# UPF_BTB_TESTBOARD.net
KiCad netlist of a schematic drawn in Altium Designer
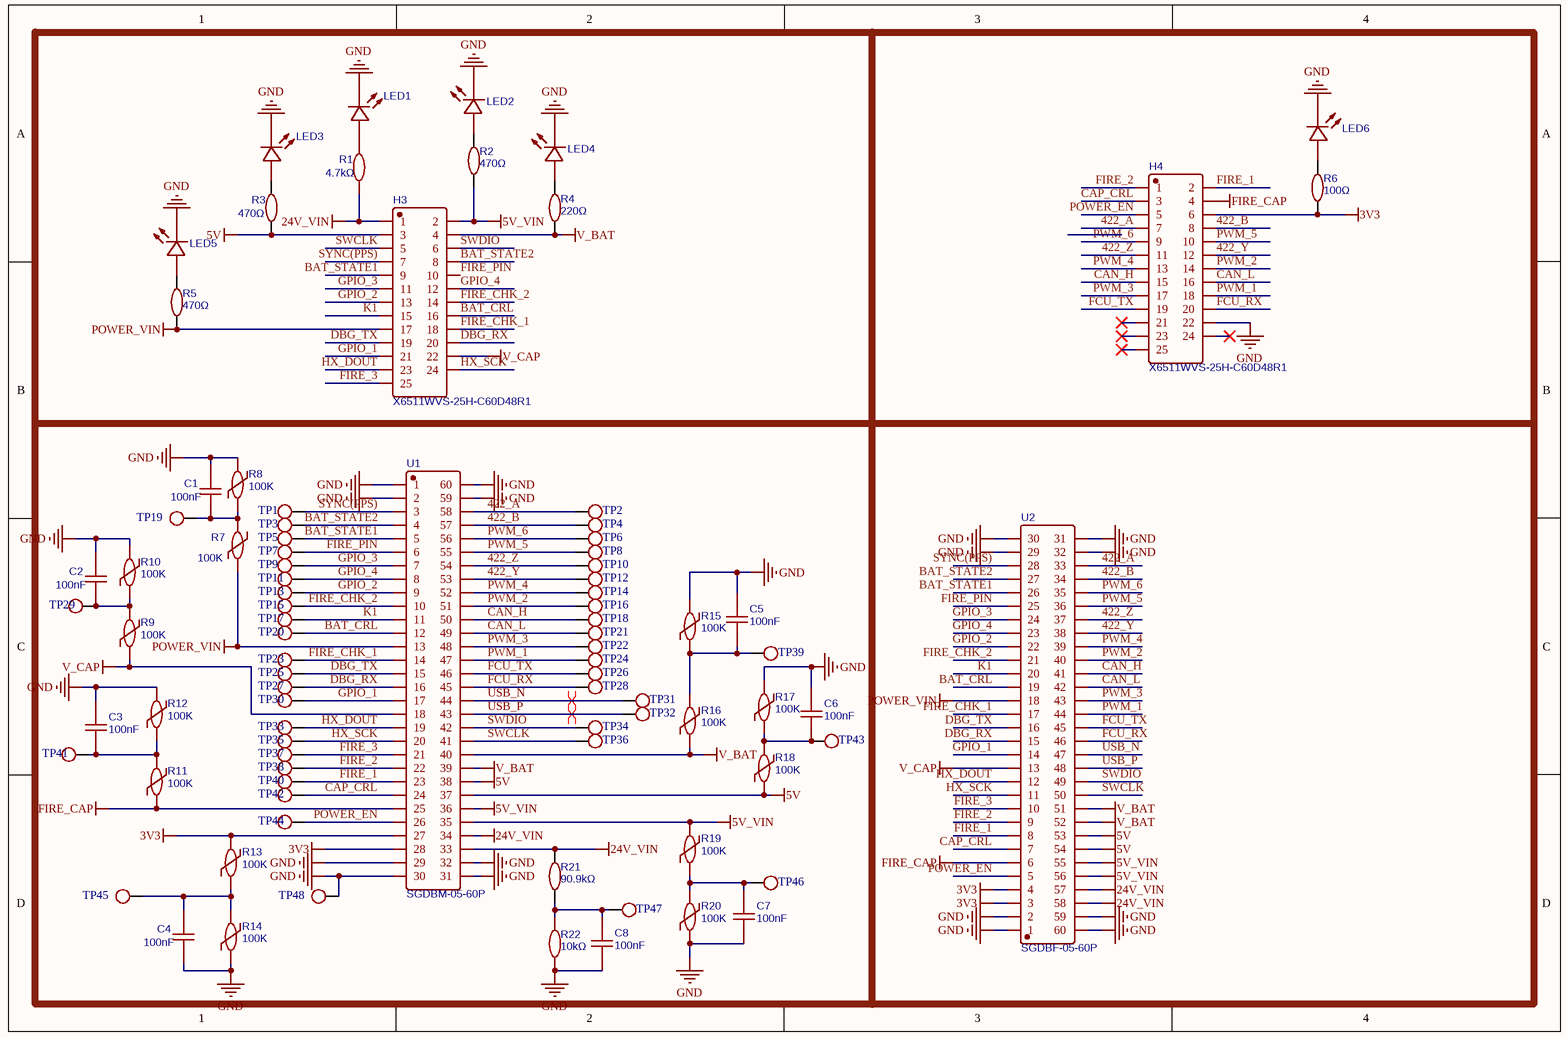
[diagram p0: UPF_BTB_TESTBOARD.SchDoc]

(export (version "E")
  (design (tool "Eeschema 10.0.6"))
  (components
    (comp (ref "C1")
      (value "100nF")
      (footprint "C0603")
      (fields
        (field (name "BOM_SUPPLIER PART") "C327087")
        (field (name "BOM_MANUFACTURER PART") "CC0603JRX7R8BB104")
        (field (name "CONTRIBUTOR") "LCSC")
      )
      (libsource (lib "C0603_100nF") (part "100nF"))
    )
    (comp (ref "C2")
      (value "100nF")
      (footprint "C0603")
      (fields
        (field (name "BOM_SUPPLIER PART") "C327087")
        (field (name "BOM_MANUFACTURER PART") "CC0603JRX7R8BB104")
        (field (name "CONTRIBUTOR") "LCSC")
      )
      (libsource (lib "C0603_100nF") (part "100nF"))
    )
    (comp (ref "C3")
      (value "100nF")
      (footprint "C0603")
      (fields
        (field (name "BOM_SUPPLIER PART") "C327087")
        (field (name "BOM_MANUFACTURER PART") "CC0603JRX7R8BB104")
        (field (name "CONTRIBUTOR") "LCSC")
      )
      (libsource (lib "C0603_100nF") (part "100nF"))
    )
    (comp (ref "C4")
      (value "100nF")
      (footprint "C0603")
      (fields
        (field (name "BOM_SUPPLIER PART") "C327087")
        (field (name "BOM_MANUFACTURER PART") "CC0603JRX7R8BB104")
        (field (name "CONTRIBUTOR") "LCSC")
      )
      (libsource (lib "C0603_100nF") (part "100nF"))
    )
    (comp (ref "C5")
      (value "100nF")
      (footprint "C0603")
      (fields
        (field (name "BOM_SUPPLIER PART") "C327087")
        (field (name "BOM_MANUFACTURER PART") "CC0603JRX7R8BB104")
        (field (name "CONTRIBUTOR") "LCSC")
      )
      (libsource (lib "C0603_100nF") (part "100nF"))
    )
    (comp (ref "C6")
      (value "100nF")
      (footprint "C0603")
      (fields
        (field (name "BOM_SUPPLIER PART") "C327087")
        (field (name "BOM_MANUFACTURER PART") "CC0603JRX7R8BB104")
        (field (name "CONTRIBUTOR") "LCSC")
      )
      (libsource (lib "C0603_100nF") (part "100nF"))
    )
    (comp (ref "C7")
      (value "100nF")
      (footprint "C0603")
      (fields
        (field (name "BOM_SUPPLIER PART") "C327087")
        (field (name "BOM_MANUFACTURER PART") "CC0603JRX7R8BB104")
        (field (name "CONTRIBUTOR") "LCSC")
      )
      (libsource (lib "C0603_100nF") (part "100nF"))
    )
    (comp (ref "C8")
      (value "100nF")
      (footprint "C0603")
      (fields
        (field (name "BOM_SUPPLIER PART") "C327087")
        (field (name "BOM_MANUFACTURER PART") "CC0603JRX7R8BB104")
        (field (name "CONTRIBUTOR") "LCSC")
      )
      (libsource (lib "C0603_100nF") (part "100nF"))
    )
    (comp (ref "H3")
      (value "X6511WVS-25H-C60D48R1")
      (footprint "HDR-SMD_25P-P2.54_XKB_X6511WVS-25H-C60D48R1")
      (fields (field (name "BOM_SUPPLIER PART") "C2883821") (field (name "CONTRIBUTOR") "LCSC"))
      (libsource (lib "X6511WVS-25H-C60D48R1") (part "X6511WVS-25H-C60D48R1"))
    )
    (comp (ref "H4")
      (value "X6511WVS-25H-C60D48R1")
      (footprint "HDR-SMD_25P-P2.54_XKB_X6511WVS-25H-C60D48R1")
      (fields (field (name "BOM_SUPPLIER PART") "C2883821") (field (name "CONTRIBUTOR") "LCSC"))
      (libsource (lib "X6511WVS-25H-C60D48R1") (part "X6511WVS-25H-C60D48R1"))
    )
    (comp (ref "LED1")
      (value "FC-F1005YGK-572J5")
      (footprint "LED0402-RD")
      (fields (field (name "BOM_SUPPLIER PART") "C130722") (field (name "CONTRIBUTOR") "LCSC"))
      (libsource (lib "LED_GREEN") (part "FC-F1005YGK-572J5"))
    )
    (comp (ref "LED2")
      (value "FC-F1005YGK-572J5")
      (footprint "LED0402-RD")
      (fields (field (name "BOM_SUPPLIER PART") "C130722") (field (name "CONTRIBUTOR") "LCSC"))
      (libsource (lib "LED_GREEN") (part "FC-F1005YGK-572J5"))
    )
    (comp (ref "LED3")
      (value "FC-F1005YGK-572J5")
      (footprint "LED0402-RD")
      (fields (field (name "BOM_SUPPLIER PART") "C130722") (field (name "CONTRIBUTOR") "LCSC"))
      (libsource (lib "LED_GREEN") (part "FC-F1005YGK-572J5"))
    )
    (comp (ref "LED4")
      (value "FC-F1005YGK-572J5")
      (footprint "LED0402-RD")
      (fields (field (name "BOM_SUPPLIER PART") "C130722") (field (name "CONTRIBUTOR") "LCSC"))
      (libsource (lib "LED_GREEN") (part "FC-F1005YGK-572J5"))
    )
    (comp (ref "LED5")
      (value "FC-F1005YGK-572J5")
      (footprint "LED0402-RD")
      (fields (field (name "BOM_SUPPLIER PART") "C130722") (field (name "CONTRIBUTOR") "LCSC"))
      (libsource (lib "LED_GREEN") (part "FC-F1005YGK-572J5"))
    )
    (comp (ref "LED6")
      (value "FC-F1005YGK-572J5")
      (footprint "LED0402-RD")
      (fields (field (name "BOM_SUPPLIER PART") "C130722") (field (name "CONTRIBUTOR") "LCSC"))
      (libsource (lib "LED_GREEN") (part "FC-F1005YGK-572J5"))
    )
    (comp (ref "R1")
      (value "4.7kΩ")
      (footprint "R0402")
      (fields
        (field (name "BOM_SUPPLIER PART") "C270129")
        (field (name "BOM_MANUFACTURER PART") "RMC04024.7K1%N")
        (field (name "CONTRIBUTOR") "LCSC")
      )
      (libsource (lib "R0402_4k7") (part "4.7kΩ"))
    )
    (comp (ref "R2")
      (value "470Ω")
      (footprint "R0402")
      (fields
        (field (name "BOM_MANUFACTURER PART") "CR0402FF4700G")
        (field (name "BOM_SUPPLIER PART") "C100443")
      )
      (libsource (lib "R0402_470") (part "470Ω"))
    )
    (comp (ref "R3")
      (value "470Ω")
      (footprint "R0402")
      (fields
        (field (name "BOM_MANUFACTURER PART") "CR0402FF4700G")
        (field (name "BOM_SUPPLIER PART") "C100443")
      )
      (libsource (lib "R0402_470") (part "470Ω"))
    )
    (comp (ref "R4")
      (value "220Ω")
      (footprint "R0402")
      (fields
        (field (name "BOM_MANUFACTURER PART") "CR0402FF2200G")
        (field (name "BOM_SUPPLIER PART") "C100308")
        (field (name "CONTRIBUTOR") "LCSC")
      )
      (libsource (lib "R0402_220") (part "220Ω"))
    )
    (comp (ref "R5")
      (value "470Ω")
      (footprint "R0402")
      (fields
        (field (name "BOM_MANUFACTURER PART") "CR0402FF4700G")
        (field (name "BOM_SUPPLIER PART") "C100443")
      )
      (libsource (lib "R0402_470") (part "470Ω"))
    )
    (comp (ref "R6")
      (value "100Ω")
      (footprint "R0402")
      (fields
        (field (name "BOM_MANUFACTURER PART") "CR0402FF1000G")
        (field (name "BOM_SUPPLIER PART") "C100194")
      )
      (libsource (lib "R0402_100") (part "100Ω"))
    )
    (comp (ref "R7")
      (value "100K")
      (footprint "R0603")
      (fields
        (field (name "BOM_SUPPLIER PART") "C388278")
        (field (name "BOM_MANUFACTURER PART") "TCTR0603F100KF4260T")
        (field (name "CONTRIBUTOR") "LCSC")
      )
      (libsource (lib "R0603_100K") (part "100K"))
    )
    (comp (ref "R8")
      (value "100K")
      (footprint "R0603")
      (fields
        (field (name "BOM_SUPPLIER PART") "C388278")
        (field (name "BOM_MANUFACTURER PART") "TCTR0603F100KF4260T")
        (field (name "CONTRIBUTOR") "LCSC")
      )
      (libsource (lib "R0603_100K") (part "100K"))
    )
    (comp (ref "R9")
      (value "100K")
      (footprint "R0603")
      (fields
        (field (name "BOM_SUPPLIER PART") "C388278")
        (field (name "BOM_MANUFACTURER PART") "TCTR0603F100KF4260T")
        (field (name "CONTRIBUTOR") "LCSC")
      )
      (libsource (lib "R0603_100K") (part "100K"))
    )
    (comp (ref "R10")
      (value "100K")
      (footprint "R0603")
      (fields
        (field (name "BOM_SUPPLIER PART") "C388278")
        (field (name "BOM_MANUFACTURER PART") "TCTR0603F100KF4260T")
        (field (name "CONTRIBUTOR") "LCSC")
      )
      (libsource (lib "R0603_100K") (part "100K"))
    )
    (comp (ref "R11")
      (value "100K")
      (footprint "R0603")
      (fields
        (field (name "BOM_SUPPLIER PART") "C388278")
        (field (name "BOM_MANUFACTURER PART") "TCTR0603F100KF4260T")
        (field (name "CONTRIBUTOR") "LCSC")
      )
      (libsource (lib "R0603_100K") (part "100K"))
    )
    (comp (ref "R12")
      (value "100K")
      (footprint "R0603")
      (fields
        (field (name "BOM_SUPPLIER PART") "C388278")
        (field (name "BOM_MANUFACTURER PART") "TCTR0603F100KF4260T")
        (field (name "CONTRIBUTOR") "LCSC")
      )
      (libsource (lib "R0603_100K") (part "100K"))
    )
    (comp (ref "R13")
      (value "100K")
      (footprint "R0603")
      (fields
        (field (name "BOM_SUPPLIER PART") "C388278")
        (field (name "BOM_MANUFACTURER PART") "TCTR0603F100KF4260T")
        (field (name "CONTRIBUTOR") "LCSC")
      )
      (libsource (lib "R0603_100K") (part "100K"))
    )
    (comp (ref "R14")
      (value "100K")
      (footprint "R0603")
      (fields
        (field (name "BOM_SUPPLIER PART") "C388278")
        (field (name "BOM_MANUFACTURER PART") "TCTR0603F100KF4260T")
        (field (name "CONTRIBUTOR") "LCSC")
      )
      (libsource (lib "R0603_100K") (part "100K"))
    )
    (comp (ref "R15")
      (value "100K")
      (footprint "R0603")
      (fields
        (field (name "BOM_SUPPLIER PART") "C388278")
        (field (name "BOM_MANUFACTURER PART") "TCTR0603F100KF4260T")
        (field (name "CONTRIBUTOR") "LCSC")
      )
      (libsource (lib "R0603_100K") (part "100K"))
    )
    (comp (ref "R16")
      (value "100K")
      (footprint "R0603")
      (fields
        (field (name "BOM_SUPPLIER PART") "C388278")
        (field (name "BOM_MANUFACTURER PART") "TCTR0603F100KF4260T")
        (field (name "CONTRIBUTOR") "LCSC")
      )
      (libsource (lib "R0603_100K") (part "100K"))
    )
    (comp (ref "R17")
      (value "100K")
      (footprint "R0603")
      (fields
        (field (name "BOM_SUPPLIER PART") "C388278")
        (field (name "BOM_MANUFACTURER PART") "TCTR0603F100KF4260T")
        (field (name "CONTRIBUTOR") "LCSC")
      )
      (libsource (lib "R0603_100K") (part "100K"))
    )
    (comp (ref "R18")
      (value "100K")
      (footprint "R0603")
      (fields
        (field (name "BOM_SUPPLIER PART") "C388278")
        (field (name "BOM_MANUFACTURER PART") "TCTR0603F100KF4260T")
        (field (name "CONTRIBUTOR") "LCSC")
      )
      (libsource (lib "R0603_100K") (part "100K"))
    )
    (comp (ref "R19")
      (value "100K")
      (footprint "R0603")
      (fields
        (field (name "BOM_SUPPLIER PART") "C388278")
        (field (name "BOM_MANUFACTURER PART") "TCTR0603F100KF4260T")
        (field (name "CONTRIBUTOR") "LCSC")
      )
      (libsource (lib "R0603_100K") (part "100K"))
    )
    (comp (ref "R20")
      (value "100K")
      (footprint "R0603")
      (fields
        (field (name "BOM_SUPPLIER PART") "C388278")
        (field (name "BOM_MANUFACTURER PART") "TCTR0603F100KF4260T")
        (field (name "CONTRIBUTOR") "LCSC")
      )
      (libsource (lib "R0603_100K") (part "100K"))
    )
    (comp (ref "R21")
      (value "90.9kΩ")
      (footprint "R0603")
      (fields
        (field (name "BOM_MANUFACTURER PART") "RS-03K9092FT")
        (field (name "BOM_SUPPLIER PART") "C140067")
      )
      (libsource (lib "R0603_90.9K") (part "90.9kΩ"))
    )
    (comp (ref "R22")
      (value "10kΩ")
      (footprint "R0603")
      (fields
        (field (name "BOM_SUPPLIER PART") "C188363")
        (field (name "BOM_MANUFACTURER PART") "TR0603B10KP05250.1W")
        (field (name "CONTRIBUTOR") "LCSC")
      )
      (libsource (lib "R0603_10K") (part "10kΩ"))
    )
    (comp (ref "TP1")
      (value "TP5")
      (footprint "TP2")
      (description "测试点/单焊盘")
      (libsource (lib "五金器件") (part "TP5"))
    )
    (comp (ref "TP2")
      (value "TP5")
      (footprint "TP2")
      (description "测试点/单焊盘")
      (libsource (lib "五金器件") (part "TP5"))
    )
    (comp (ref "TP3")
      (value "TP5")
      (footprint "TP2")
      (description "测试点/单焊盘")
      (libsource (lib "五金器件") (part "TP5"))
    )
    (comp (ref "TP4")
      (value "TP5")
      (footprint "TP2")
      (description "测试点/单焊盘")
      (libsource (lib "五金器件") (part "TP5"))
    )
    (comp (ref "TP5")
      (value "TP5")
      (footprint "TP2")
      (description "测试点/单焊盘")
      (libsource (lib "五金器件") (part "TP5"))
    )
    (comp (ref "TP6")
      (value "TP5")
      (footprint "TP2")
      (description "测试点/单焊盘")
      (libsource (lib "五金器件") (part "TP5"))
    )
    (comp (ref "TP7")
      (value "TP5")
      (footprint "TP2")
      (description "测试点/单焊盘")
      (libsource (lib "五金器件") (part "TP5"))
    )
    (comp (ref "TP8")
      (value "TP5")
      (footprint "TP2")
      (description "测试点/单焊盘")
      (libsource (lib "五金器件") (part "TP5"))
    )
    (comp (ref "TP9")
      (value "TP5")
      (footprint "TP2")
      (description "测试点/单焊盘")
      (libsource (lib "五金器件") (part "TP5"))
    )
    (comp (ref "TP10")
      (value "TP5")
      (footprint "TP2")
      (description "测试点/单焊盘")
      (libsource (lib "五金器件") (part "TP5"))
    )
    (comp (ref "TP11")
      (value "TP5")
      (footprint "TP2")
      (description "测试点/单焊盘")
      (libsource (lib "五金器件") (part "TP5"))
    )
    (comp (ref "TP12")
      (value "TP5")
      (footprint "TP2")
      (description "测试点/单焊盘")
      (libsource (lib "五金器件") (part "TP5"))
    )
    (comp (ref "TP13")
      (value "TP5")
      (footprint "TP2")
      (description "测试点/单焊盘")
      (libsource (lib "五金器件") (part "TP5"))
    )
    (comp (ref "TP14")
      (value "TP5")
      (footprint "TP2")
      (description "测试点/单焊盘")
      (libsource (lib "五金器件") (part "TP5"))
    )
    (comp (ref "TP15")
      (value "TP5")
      (footprint "TP2")
      (description "测试点/单焊盘")
      (libsource (lib "五金器件") (part "TP5"))
    )
    (comp (ref "TP16")
      (value "TP5")
      (footprint "TP2")
      (description "测试点/单焊盘")
      (libsource (lib "五金器件") (part "TP5"))
    )
    (comp (ref "TP17")
      (value "TP5")
      (footprint "TP2")
      (description "测试点/单焊盘")
      (libsource (lib "五金器件") (part "TP5"))
    )
    (comp (ref "TP18")
      (value "TP5")
      (footprint "TP2")
      (description "测试点/单焊盘")
      (libsource (lib "五金器件") (part "TP5"))
    )
    (comp (ref "TP19")
      (value "TP5")
      (footprint "TP2")
      (description "测试点/单焊盘")
      (libsource (lib "五金器件") (part "TP5"))
    )
    (comp (ref "TP20")
      (value "TP5")
      (footprint "TP2")
      (description "测试点/单焊盘")
      (libsource (lib "五金器件") (part "TP5"))
    )
    (comp (ref "TP21")
      (value "TP5")
      (footprint "TP2")
      (description "测试点/单焊盘")
      (libsource (lib "五金器件") (part "TP5"))
    )
    (comp (ref "TP22")
      (value "TP5")
      (footprint "TP2")
      (description "测试点/单焊盘")
      (libsource (lib "五金器件") (part "TP5"))
    )
    (comp (ref "TP23")
      (value "TP5")
      (footprint "TP2")
      (description "测试点/单焊盘")
      (libsource (lib "五金器件") (part "TP5"))
    )
    (comp (ref "TP24")
      (value "TP5")
      (footprint "TP2")
      (description "测试点/单焊盘")
      (libsource (lib "五金器件") (part "TP5"))
    )
    (comp (ref "TP25")
      (value "TP5")
      (footprint "TP2")
      (description "测试点/单焊盘")
      (libsource (lib "五金器件") (part "TP5"))
    )
    (comp (ref "TP26")
      (value "TP5")
      (footprint "TP2")
      (description "测试点/单焊盘")
      (libsource (lib "五金器件") (part "TP5"))
    )
    (comp (ref "TP27")
      (value "TP5")
      (footprint "TP2")
      (description "测试点/单焊盘")
      (libsource (lib "五金器件") (part "TP5"))
    )
    (comp (ref "TP28")
      (value "TP5")
      (footprint "TP2")
      (description "测试点/单焊盘")
      (libsource (lib "五金器件") (part "TP5"))
    )
    (comp (ref "TP29")
      (value "TP5")
      (footprint "TP2")
      (description "测试点/单焊盘")
      (libsource (lib "五金器件") (part "TP5"))
    )
    (comp (ref "TP30")
      (value "TP5")
      (footprint "TP2")
      (description "测试点/单焊盘")
      (libsource (lib "五金器件") (part "TP5"))
    )
    (comp (ref "TP31")
      (value "TP5")
      (footprint "TP2")
      (description "测试点/单焊盘")
      (libsource (lib "五金器件") (part "TP5"))
    )
    (comp (ref "TP32")
      (value "TP5")
      (footprint "TP2")
      (description "测试点/单焊盘")
      (libsource (lib "五金器件") (part "TP5"))
    )
    (comp (ref "TP33")
      (value "TP5")
      (footprint "TP2")
      (description "测试点/单焊盘")
      (libsource (lib "五金器件") (part "TP5"))
    )
    (comp (ref "TP34")
      (value "TP5")
      (footprint "TP2")
      (description "测试点/单焊盘")
      (libsource (lib "五金器件") (part "TP5"))
    )
    (comp (ref "TP35")
      (value "TP5")
      (footprint "TP2")
      (description "测试点/单焊盘")
      (libsource (lib "五金器件") (part "TP5"))
    )
    (comp (ref "TP36")
      (value "TP5")
      (footprint "TP2")
      (description "测试点/单焊盘")
      (libsource (lib "五金器件") (part "TP5"))
    )
    (comp (ref "TP37")
      (value "TP5")
      (footprint "TP2")
      (description "测试点/单焊盘")
      (libsource (lib "五金器件") (part "TP5"))
    )
    (comp (ref "TP38")
      (value "TP5")
      (footprint "TP2")
      (description "测试点/单焊盘")
      (libsource (lib "五金器件") (part "TP5"))
    )
    (comp (ref "TP39")
      (value "TP5")
      (footprint "TP2")
      (description "测试点/单焊盘")
      (libsource (lib "五金器件") (part "TP5"))
    )
    (comp (ref "TP40")
      (value "TP5")
      (footprint "TP2")
      (description "测试点/单焊盘")
      (libsource (lib "五金器件") (part "TP5"))
    )
    (comp (ref "TP41")
      (value "TP5")
      (footprint "TP2")
      (description "测试点/单焊盘")
      (libsource (lib "五金器件") (part "TP5"))
    )
    (comp (ref "TP42")
      (value "TP5")
      (footprint "TP2")
      (description "测试点/单焊盘")
      (libsource (lib "五金器件") (part "TP5"))
    )
    (comp (ref "TP43")
      (value "TP5")
      (footprint "TP2")
      (description "测试点/单焊盘")
      (libsource (lib "五金器件") (part "TP5"))
    )
    (comp (ref "TP44")
      (value "TP5")
      (footprint "TP2")
      (description "测试点/单焊盘")
      (libsource (lib "五金器件") (part "TP5"))
    )
    (comp (ref "TP45")
      (value "TP5")
      (footprint "TP2")
      (description "测试点/单焊盘")
      (libsource (lib "五金器件") (part "TP5"))
    )
    (comp (ref "TP46")
      (value "TP5")
      (footprint "TP2")
      (description "测试点/单焊盘")
      (libsource (lib "五金器件") (part "TP5"))
    )
    (comp (ref "TP47")
      (value "TP5")
      (footprint "TP2")
      (description "测试点/单焊盘")
      (libsource (lib "五金器件") (part "TP5"))
    )
    (comp (ref "TP48")
      (value "TP5")
      (footprint "TP2")
      (description "测试点/单焊盘")
      (libsource (lib "五金器件") (part "TP5"))
    )
    (comp (ref "U1")
      (value "SGDBM-05-60P")
      (footprint "HG-SGDBM-0.5_60P")
      (fields (field (name "BOM_SUPPLIER PART") "C9900010919") (field (name "CONTRIBUTOR") "LCSC"))
      (libsource (lib "SGDBM-05-60P") (part "SGDBM-05-60P"))
    )
    (comp (ref "U2")
      (value "SGDBF-05-60P")
      (footprint "HG-SGDBF-0.5_60P")
      (fields
        (field (name "BOM_SUPPLIER PART") "C9900010919")
        (field (name "BOM_MANUFACTURER PART") "SGDBM-05-60P")
        (field (name "CONTRIBUTOR") "LCSC")
      )
      (libsource (lib "SGDBM-05-60P") (part "SGDBM-05-60P"))
    )
  )
  (nets
    (net (code "1") (name "/422_A") (class "Default")
      (node (ref "H4") (pin "7") (pinfunction "7_7") (pintype "passive"))
      (node (ref "TP2") (pin "1") (pintype "passive"))
      (node (ref "U1") (pin "58") (pinfunction "58_58") (pintype "passive"))
      (node (ref "U2") (pin "33") (pinfunction "33_33") (pintype "passive"))
    )
    (net (code "2") (name "/422_B") (class "Default")
      (node (ref "H4") (pin "8") (pinfunction "8_8") (pintype "passive"))
      (node (ref "TP4") (pin "1") (pintype "passive"))
      (node (ref "U1") (pin "57") (pinfunction "57_57") (pintype "passive"))
      (node (ref "U2") (pin "34") (pinfunction "34_34") (pintype "passive"))
    )
    (net (code "3") (name "/422_Y") (class "Default")
      (node (ref "H4") (pin "12") (pinfunction "12_12") (pintype "passive"))
      (node (ref "TP12") (pin "1") (pintype "passive"))
      (node (ref "U1") (pin "53") (pinfunction "53_53") (pintype "passive"))
      (node (ref "U2") (pin "38") (pinfunction "38_38") (pintype "passive"))
    )
    (net (code "4") (name "/422_Z") (class "Default")
      (node (ref "H4") (pin "11") (pinfunction "11_11") (pintype "passive"))
      (node (ref "TP10") (pin "1") (pintype "passive"))
      (node (ref "U1") (pin "54") (pinfunction "54_54") (pintype "passive"))
      (node (ref "U2") (pin "37") (pinfunction "37_37") (pintype "passive"))
    )
    (net (code "5") (name "/BAT_CRL") (class "Default")
      (node (ref "H3") (pin "16") (pinfunction "16_16") (pintype "passive"))
      (node (ref "TP20") (pin "1") (pintype "passive"))
      (node (ref "U1") (pin "12") (pinfunction "12_12") (pintype "passive"))
      (node (ref "U2") (pin "19") (pinfunction "19_19") (pintype "passive"))
    )
    (net (code "6") (name "/BAT_STATE1") (class "Default")
      (node (ref "H3") (pin "9") (pinfunction "9_9") (pintype "passive"))
      (node (ref "TP5") (pin "1") (pintype "passive"))
      (node (ref "U1") (pin "5") (pinfunction "5_5") (pintype "passive"))
      (node (ref "U2") (pin "26") (pinfunction "26_26") (pintype "passive"))
    )
    (net (code "7") (name "/BAT_STATE2") (class "Default")
      (node (ref "H3") (pin "8") (pinfunction "8_8") (pintype "passive"))
      (node (ref "TP3") (pin "1") (pintype "passive"))
      (node (ref "U1") (pin "4") (pinfunction "4_4") (pintype "passive"))
      (node (ref "U2") (pin "27") (pinfunction "27_27") (pintype "passive"))
    )
    (net (code "8") (name "/CAN_H") (class "Default")
      (node (ref "H4") (pin "15") (pinfunction "15_15") (pintype "passive"))
      (node (ref "TP18") (pin "1") (pintype "passive"))
      (node (ref "U1") (pin "50") (pinfunction "50_50") (pintype "passive"))
      (node (ref "U2") (pin "41") (pinfunction "41_41") (pintype "passive"))
    )
    (net (code "9") (name "/CAN_L") (class "Default")
      (node (ref "H4") (pin "16") (pinfunction "16_16") (pintype "passive"))
      (node (ref "TP21") (pin "1") (pintype "passive"))
      (node (ref "U1") (pin "49") (pinfunction "49_49") (pintype "passive"))
      (node (ref "U2") (pin "42") (pinfunction "42_42") (pintype "passive"))
    )
    (net (code "10") (name "/CAP_CRL") (class "Default")
      (node (ref "H4") (pin "3") (pinfunction "3_3") (pintype "passive"))
      (node (ref "TP42") (pin "1") (pintype "passive"))
      (node (ref "U1") (pin "24") (pinfunction "24_24") (pintype "passive"))
      (node (ref "U2") (pin "7") (pinfunction "7_7") (pintype "passive"))
    )
    (net (code "11") (name "/DBG_RX") (class "Default")
      (node (ref "H3") (pin "20") (pinfunction "20_20") (pintype "passive"))
      (node (ref "TP27") (pin "1") (pintype "passive"))
      (node (ref "U1") (pin "16") (pinfunction "16_16") (pintype "passive"))
      (node (ref "U2") (pin "15") (pinfunction "15_15") (pintype "passive"))
    )
    (net (code "12") (name "/DBG_TX") (class "Default")
      (node (ref "H3") (pin "19") (pinfunction "19_19") (pintype "passive"))
      (node (ref "TP25") (pin "1") (pintype "passive"))
      (node (ref "U1") (pin "15") (pinfunction "15_15") (pintype "passive"))
      (node (ref "U2") (pin "16") (pinfunction "16_16") (pintype "passive"))
    )
    (net (code "13") (name "/FCU_RX") (class "Default")
      (node (ref "H4") (pin "20") (pinfunction "20_20") (pintype "passive"))
      (node (ref "TP28") (pin "1") (pintype "passive"))
      (node (ref "U1") (pin "45") (pinfunction "45_45") (pintype "passive"))
      (node (ref "U2") (pin "46") (pinfunction "46_46") (pintype "passive"))
    )
    (net (code "14") (name "/FCU_TX") (class "Default")
      (node (ref "H4") (pin "19") (pinfunction "19_19") (pintype "passive"))
      (node (ref "TP26") (pin "1") (pintype "passive"))
      (node (ref "U1") (pin "46") (pinfunction "46_46") (pintype "passive"))
      (node (ref "U2") (pin "45") (pinfunction "45_45") (pintype "passive"))
    )
    (net (code "15") (name "/FIRE_1") (class "Default")
      (node (ref "H4") (pin "2") (pinfunction "2_2") (pintype "passive"))
      (node (ref "TP40") (pin "1") (pintype "passive"))
      (node (ref "U1") (pin "23") (pinfunction "23_23") (pintype "passive"))
      (node (ref "U2") (pin "8") (pinfunction "8_8") (pintype "passive"))
    )
    (net (code "16") (name "/FIRE_2") (class "Default")
      (node (ref "H4") (pin "1") (pinfunction "1_1") (pintype "passive"))
      (node (ref "TP38") (pin "1") (pintype "passive"))
      (node (ref "U1") (pin "22") (pinfunction "22_22") (pintype "passive"))
      (node (ref "U2") (pin "9") (pinfunction "9_9") (pintype "passive"))
    )
    (net (code "17") (name "/FIRE_3") (class "Default")
      (node (ref "H3") (pin "25") (pinfunction "25_25") (pintype "passive"))
      (node (ref "TP37") (pin "1") (pintype "passive"))
      (node (ref "U1") (pin "21") (pinfunction "21_21") (pintype "passive"))
      (node (ref "U2") (pin "10") (pinfunction "10_10") (pintype "passive"))
    )
    (net (code "18") (name "/FIRE_CHK_1") (class "Default")
      (node (ref "H3") (pin "18") (pinfunction "18_18") (pintype "passive"))
      (node (ref "TP23") (pin "1") (pintype "passive"))
      (node (ref "U1") (pin "14") (pinfunction "14_14") (pintype "passive"))
      (node (ref "U2") (pin "17") (pinfunction "17_17") (pintype "passive"))
    )
    (net (code "19") (name "/FIRE_CHK_2") (class "Default")
      (node (ref "H3") (pin "14") (pinfunction "14_14") (pintype "passive"))
      (node (ref "TP15") (pin "1") (pintype "passive"))
      (node (ref "U1") (pin "10") (pinfunction "10_10") (pintype "passive"))
      (node (ref "U2") (pin "21") (pinfunction "21_21") (pintype "passive"))
    )
    (net (code "20") (name "/FIRE_PIN") (class "Default")
      (node (ref "H3") (pin "10") (pinfunction "10_10") (pintype "passive"))
      (node (ref "TP7") (pin "1") (pintype "passive"))
      (node (ref "U1") (pin "6") (pinfunction "6_6") (pintype "passive"))
      (node (ref "U2") (pin "25") (pinfunction "25_25") (pintype "passive"))
    )
    (net (code "21") (name "/GPIO_1") (class "Default")
      (node (ref "H3") (pin "21") (pinfunction "21_21") (pintype "passive"))
      (node (ref "TP30") (pin "1") (pintype "passive"))
      (node (ref "U1") (pin "17") (pinfunction "17_17") (pintype "passive"))
      (node (ref "U2") (pin "14") (pinfunction "14_14") (pintype "passive"))
    )
    (net (code "22") (name "/GPIO_2") (class "Default")
      (node (ref "H3") (pin "13") (pinfunction "13_13") (pintype "passive"))
      (node (ref "TP13") (pin "1") (pintype "passive"))
      (node (ref "U1") (pin "9") (pinfunction "9_9") (pintype "passive"))
      (node (ref "U2") (pin "22") (pinfunction "22_22") (pintype "passive"))
    )
    (net (code "23") (name "/GPIO_3") (class "Default")
      (node (ref "H3") (pin "11") (pinfunction "11_11") (pintype "passive"))
      (node (ref "TP9") (pin "1") (pintype "passive"))
      (node (ref "U1") (pin "7") (pinfunction "7_7") (pintype "passive"))
      (node (ref "U2") (pin "24") (pinfunction "24_24") (pintype "passive"))
    )
    (net (code "24") (name "/GPIO_4") (class "Default")
      (node (ref "H3") (pin "12") (pinfunction "12_12") (pintype "passive"))
      (node (ref "TP11") (pin "1") (pintype "passive"))
      (node (ref "U1") (pin "8") (pinfunction "8_8") (pintype "passive"))
      (node (ref "U2") (pin "23") (pinfunction "23_23") (pintype "passive"))
    )
    (net (code "25") (name "/HX_DOUT") (class "Default")
      (node (ref "H3") (pin "23") (pinfunction "23_23") (pintype "passive"))
      (node (ref "TP33") (pin "1") (pintype "passive"))
      (node (ref "U1") (pin "19") (pinfunction "19_19") (pintype "passive"))
      (node (ref "U2") (pin "12") (pinfunction "12_12") (pintype "passive"))
    )
    (net (code "26") (name "/HX_SCK") (class "Default")
      (node (ref "H3") (pin "24") (pinfunction "24_24") (pintype "passive"))
      (node (ref "TP35") (pin "1") (pintype "passive"))
      (node (ref "U1") (pin "20") (pinfunction "20_20") (pintype "passive"))
      (node (ref "U2") (pin "11") (pinfunction "11_11") (pintype "passive"))
    )
    (net (code "27") (name "/K1") (class "Default")
      (node (ref "H3") (pin "15") (pinfunction "15_15") (pintype "passive"))
      (node (ref "TP17") (pin "1") (pintype "passive"))
      (node (ref "U1") (pin "11") (pinfunction "11_11") (pintype "passive"))
      (node (ref "U2") (pin "20") (pinfunction "20_20") (pintype "passive"))
    )
    (net (code "28") (name "/POWER_EN") (class "Default")
      (node (ref "H4") (pin "5") (pinfunction "5_5") (pintype "passive"))
      (node (ref "TP44") (pin "1") (pintype "passive"))
      (node (ref "U1") (pin "26") (pinfunction "26_26") (pintype "passive"))
      (node (ref "U2") (pin "5") (pinfunction "5_5") (pintype "passive"))
    )
    (net (code "29") (name "/PWM_1") (class "Default")
      (node (ref "H4") (pin "18") (pinfunction "18_18") (pintype "passive"))
      (node (ref "TP24") (pin "1") (pintype "passive"))
      (node (ref "U1") (pin "47") (pinfunction "47_47") (pintype "passive"))
      (node (ref "U2") (pin "44") (pinfunction "44_44") (pintype "passive"))
    )
    (net (code "30") (name "/PWM_2") (class "Default")
      (node (ref "H4") (pin "14") (pinfunction "14_14") (pintype "passive"))
      (node (ref "TP16") (pin "1") (pintype "passive"))
      (node (ref "U1") (pin "51") (pinfunction "51_51") (pintype "passive"))
      (node (ref "U2") (pin "40") (pinfunction "40_40") (pintype "passive"))
    )
    (net (code "31") (name "/PWM_3") (class "Default")
      (node (ref "H4") (pin "17") (pinfunction "17_17") (pintype "passive"))
      (node (ref "TP22") (pin "1") (pintype "passive"))
      (node (ref "U1") (pin "48") (pinfunction "48_48") (pintype "passive"))
      (node (ref "U2") (pin "43") (pinfunction "43_43") (pintype "passive"))
    )
    (net (code "32") (name "/PWM_4") (class "Default")
      (node (ref "H4") (pin "13") (pinfunction "13_13") (pintype "passive"))
      (node (ref "TP14") (pin "1") (pintype "passive"))
      (node (ref "U1") (pin "52") (pinfunction "52_52") (pintype "passive"))
      (node (ref "U2") (pin "39") (pinfunction "39_39") (pintype "passive"))
    )
    (net (code "33") (name "/PWM_5") (class "Default")
      (node (ref "H4") (pin "10") (pinfunction "10_10") (pintype "passive"))
      (node (ref "TP8") (pin "1") (pintype "passive"))
      (node (ref "U1") (pin "55") (pinfunction "55_55") (pintype "passive"))
      (node (ref "U2") (pin "36") (pinfunction "36_36") (pintype "passive"))
    )
    (net (code "34") (name "/PWM_6") (class "Default")
      (node (ref "H4") (pin "9") (pinfunction "9_9") (pintype "passive"))
      (node (ref "TP6") (pin "1") (pintype "passive"))
      (node (ref "U1") (pin "56") (pinfunction "56_56") (pintype "passive"))
      (node (ref "U2") (pin "35") (pinfunction "35_35") (pintype "passive"))
    )
    (net (code "35") (name "/SWCLK") (class "Default")
      (node (ref "H3") (pin "5") (pinfunction "5_5") (pintype "passive"))
      (node (ref "TP36") (pin "1") (pintype "passive"))
      (node (ref "U1") (pin "41") (pinfunction "41_41") (pintype "passive"))
      (node (ref "U2") (pin "50") (pinfunction "50_50") (pintype "passive"))
    )
    (net (code "36") (name "/SWDIO") (class "Default")
      (node (ref "H3") (pin "6") (pinfunction "6_6") (pintype "passive"))
      (node (ref "TP34") (pin "1") (pintype "passive"))
      (node (ref "U1") (pin "42") (pinfunction "42_42") (pintype "passive"))
      (node (ref "U2") (pin "49") (pinfunction "49_49") (pintype "passive"))
    )
    (net (code "37") (name "/SYNC(PPS)") (class "Default")
      (node (ref "H3") (pin "7") (pinfunction "7_7") (pintype "passive"))
      (node (ref "TP1") (pin "1") (pintype "passive"))
      (node (ref "U1") (pin "3") (pinfunction "3_3") (pintype "passive"))
      (node (ref "U2") (pin "28") (pinfunction "28_28") (pintype "passive"))
    )
    (net (code "38") (name "/USB_N") (class "Default")
      (node (ref "TP31") (pin "1") (pintype "passive"))
      (node (ref "U1") (pin "44") (pinfunction "44_44") (pintype "passive"))
      (node (ref "U2") (pin "47") (pinfunction "47_47") (pintype "passive"))
    )
    (net (code "39") (name "/USB_P") (class "Default")
      (node (ref "TP32") (pin "1") (pintype "passive"))
      (node (ref "U1") (pin "43") (pinfunction "43_43") (pintype "passive"))
      (node (ref "U2") (pin "48") (pinfunction "48_48") (pintype "passive"))
    )
    (net (code "40") (name "3V3") (class "Default")
      (node (ref "H4") (pin "6") (pinfunction "6_6") (pintype "passive"))
      (node (ref "R13") (pin "2") (pinfunction "2_2") (pintype "passive"))
      (node (ref "R6") (pin "2") (pinfunction "2_2") (pintype "passive"))
      (node (ref "U1") (pin "27") (pinfunction "27_27") (pintype "passive"))
      (node (ref "U1") (pin "28") (pinfunction "28_28") (pintype "passive"))
      (node (ref "U2") (pin "3") (pinfunction "3_3") (pintype "passive"))
      (node (ref "U2") (pin "4") (pinfunction "4_4") (pintype "passive"))
    )
    (net (code "41") (name "5V") (class "Default")
      (node (ref "H3") (pin "3") (pinfunction "3_3") (pintype "passive"))
      (node (ref "R18") (pin "1") (pinfunction "1_1") (pintype "passive"))
      (node (ref "R3") (pin "2") (pinfunction "2_2") (pintype "passive"))
      (node (ref "U1") (pin "37") (pinfunction "37_37") (pintype "passive"))
      (node (ref "U1") (pin "38") (pinfunction "38_38") (pintype "passive"))
      (node (ref "U2") (pin "53") (pinfunction "53_53") (pintype "passive"))
      (node (ref "U2") (pin "54") (pinfunction "54_54") (pintype "passive"))
    )
    (net (code "42") (name "5V_VIN") (class "Default")
      (node (ref "H3") (pin "2") (pinfunction "2_2") (pintype "passive"))
      (node (ref "R19") (pin "2") (pinfunction "2_2") (pintype "passive"))
      (node (ref "R2") (pin "1") (pinfunction "1_1") (pintype "passive"))
      (node (ref "U1") (pin "35") (pinfunction "35_35") (pintype "passive"))
      (node (ref "U1") (pin "36") (pinfunction "36_36") (pintype "passive"))
      (node (ref "U2") (pin "55") (pinfunction "55_55") (pintype "passive"))
      (node (ref "U2") (pin "56") (pinfunction "56_56") (pintype "passive"))
    )
    (net (code "43") (name "24V_VIN") (class "Default")
      (node (ref "H3") (pin "1") (pinfunction "1_1") (pintype "passive"))
      (node (ref "R1") (pin "1") (pinfunction "1_1") (pintype "passive"))
      (node (ref "R21") (pin "2") (pinfunction "2_2") (pintype "passive"))
      (node (ref "U1") (pin "33") (pinfunction "33_33") (pintype "passive"))
      (node (ref "U1") (pin "34") (pinfunction "34_34") (pintype "passive"))
      (node (ref "U2") (pin "57") (pinfunction "57_57") (pintype "passive"))
      (node (ref "U2") (pin "58") (pinfunction "58_58") (pintype "passive"))
    )
    (net (code "44") (name "FIRE_CAP") (class "Default")
      (node (ref "H4") (pin "4") (pinfunction "4_4") (pintype "passive"))
      (node (ref "R11") (pin "1") (pinfunction "1_1") (pintype "passive"))
      (node (ref "U1") (pin "25") (pinfunction "25_25") (pintype "passive"))
      (node (ref "U2") (pin "6") (pinfunction "6_6") (pintype "passive"))
    )
    (net (code "45") (name "GND") (class "Default")
      (node (ref "C1") (pin "1") (pinfunction "1_1") (pintype "passive"))
      (node (ref "C2") (pin "1") (pinfunction "1_1") (pintype "passive"))
      (node (ref "C3") (pin "2") (pinfunction "2_2") (pintype "passive"))
      (node (ref "C4") (pin "2") (pinfunction "2_2") (pintype "passive"))
      (node (ref "C5") (pin "1") (pinfunction "1_1") (pintype "passive"))
      (node (ref "C6") (pin "1") (pinfunction "1_1") (pintype "passive"))
      (node (ref "C7") (pin "2") (pinfunction "2_2") (pintype "passive"))
      (node (ref "C8") (pin "2") (pinfunction "2_2") (pintype "passive"))
      (node (ref "H4") (pin "22") (pinfunction "22_22") (pintype "passive"))
      (node (ref "LED1") (pin "1") (pinfunction "K_1") (pintype "passive"))
      (node (ref "LED2") (pin "1") (pinfunction "K_1") (pintype "passive"))
      (node (ref "LED3") (pin "1") (pinfunction "K_1") (pintype "passive"))
      (node (ref "LED4") (pin "1") (pinfunction "K_1") (pintype "passive"))
      (node (ref "LED5") (pin "1") (pinfunction "K_1") (pintype "passive"))
      (node (ref "LED6") (pin "1") (pinfunction "K_1") (pintype "passive"))
      (node (ref "R10") (pin "2") (pinfunction "2_2") (pintype "passive"))
      (node (ref "R12") (pin "2") (pinfunction "2_2") (pintype "passive"))
      (node (ref "R14") (pin "1") (pinfunction "1_1") (pintype "passive"))
      (node (ref "R15") (pin "2") (pinfunction "2_2") (pintype "passive"))
      (node (ref "R17") (pin "2") (pinfunction "2_2") (pintype "passive"))
      (node (ref "R20") (pin "1") (pinfunction "1_1") (pintype "passive"))
      (node (ref "R22") (pin "1") (pinfunction "1_1") (pintype "passive"))
      (node (ref "R8") (pin "2") (pinfunction "2_2") (pintype "passive"))
      (node (ref "TP48") (pin "1") (pintype "passive"))
      (node (ref "U1") (pin "1") (pinfunction "1_1") (pintype "passive"))
      (node (ref "U1") (pin "2") (pinfunction "2_2") (pintype "passive"))
      (node (ref "U1") (pin "29") (pinfunction "29_29") (pintype "passive"))
      (node (ref "U1") (pin "30") (pinfunction "30_30") (pintype "passive"))
      (node (ref "U1") (pin "31") (pinfunction "31_31") (pintype "passive"))
      (node (ref "U1") (pin "32") (pinfunction "32_32") (pintype "passive"))
      (node (ref "U1") (pin "59") (pinfunction "59_59") (pintype "passive"))
      (node (ref "U1") (pin "60") (pinfunction "60_60") (pintype "passive"))
      (node (ref "U2") (pin "1") (pinfunction "1_1") (pintype "passive"))
      (node (ref "U2") (pin "2") (pinfunction "2_2") (pintype "passive"))
      (node (ref "U2") (pin "29") (pinfunction "29_29") (pintype "passive"))
      (node (ref "U2") (pin "30") (pinfunction "30_30") (pintype "passive"))
      (node (ref "U2") (pin "31") (pinfunction "31_31") (pintype "passive"))
      (node (ref "U2") (pin "32") (pinfunction "32_32") (pintype "passive"))
      (node (ref "U2") (pin "59") (pinfunction "59_59") (pintype "passive"))
      (node (ref "U2") (pin "60") (pinfunction "60_60") (pintype "passive"))
    )
    (net (code "46") (name "Net-(C1-Pad2)") (class "Default")
      (node (ref "C1") (pin "2") (pinfunction "2_2") (pintype "passive"))
      (node (ref "R7") (pin "2") (pinfunction "2_2") (pintype "passive"))
      (node (ref "R8") (pin "1") (pinfunction "1_1") (pintype "passive"))
      (node (ref "TP19") (pin "1") (pintype "passive"))
    )
    (net (code "47") (name "Net-(C2-Pad2)") (class "Default")
      (node (ref "C2") (pin "2") (pinfunction "2_2") (pintype "passive"))
      (node (ref "R10") (pin "1") (pinfunction "1_1") (pintype "passive"))
      (node (ref "R9") (pin "2") (pinfunction "2_2") (pintype "passive"))
      (node (ref "TP29") (pin "1") (pintype "passive"))
    )
    (net (code "48") (name "Net-(C3-Pad1)") (class "Default")
      (node (ref "C3") (pin "1") (pinfunction "1_1") (pintype "passive"))
      (node (ref "R11") (pin "2") (pinfunction "2_2") (pintype "passive"))
      (node (ref "R12") (pin "1") (pinfunction "1_1") (pintype "passive"))
      (node (ref "TP41") (pin "1") (pintype "passive"))
    )
    (net (code "49") (name "Net-(C4-Pad1)") (class "Default")
      (node (ref "C4") (pin "1") (pinfunction "1_1") (pintype "passive"))
      (node (ref "R13") (pin "1") (pinfunction "1_1") (pintype "passive"))
      (node (ref "R14") (pin "2") (pinfunction "2_2") (pintype "passive"))
      (node (ref "TP45") (pin "1") (pintype "passive"))
    )
    (net (code "50") (name "Net-(C5-Pad2)") (class "Default")
      (node (ref "C5") (pin "2") (pinfunction "2_2") (pintype "passive"))
      (node (ref "R15") (pin "1") (pinfunction "1_1") (pintype "passive"))
      (node (ref "R16") (pin "2") (pinfunction "2_2") (pintype "passive"))
      (node (ref "TP39") (pin "1") (pintype "passive"))
    )
    (net (code "51") (name "Net-(C6-Pad2)") (class "Default")
      (node (ref "C6") (pin "2") (pinfunction "2_2") (pintype "passive"))
      (node (ref "R17") (pin "1") (pinfunction "1_1") (pintype "passive"))
      (node (ref "R18") (pin "2") (pinfunction "2_2") (pintype "passive"))
      (node (ref "TP43") (pin "1") (pintype "passive"))
    )
    (net (code "52") (name "Net-(C7-Pad1)") (class "Default")
      (node (ref "C7") (pin "1") (pinfunction "1_1") (pintype "passive"))
      (node (ref "R19") (pin "1") (pinfunction "1_1") (pintype "passive"))
      (node (ref "R20") (pin "2") (pinfunction "2_2") (pintype "passive"))
      (node (ref "TP46") (pin "1") (pintype "passive"))
    )
    (net (code "53") (name "Net-(C8-Pad1)") (class "Default")
      (node (ref "C8") (pin "1") (pinfunction "1_1") (pintype "passive"))
      (node (ref "R21") (pin "1") (pinfunction "1_1") (pintype "passive"))
      (node (ref "R22") (pin "2") (pinfunction "2_2") (pintype "passive"))
      (node (ref "TP47") (pin "1") (pintype "passive"))
    )
    (net (code "54") (name "Net-(LED1-A)") (class "Default")
      (node (ref "LED1") (pin "2") (pinfunction "A_2") (pintype "passive"))
      (node (ref "R1") (pin "2") (pinfunction "2_2") (pintype "passive"))
    )
    (net (code "55") (name "Net-(LED2-A)") (class "Default")
      (node (ref "LED2") (pin "2") (pinfunction "A_2") (pintype "passive"))
      (node (ref "R2") (pin "2") (pinfunction "2_2") (pintype "passive"))
    )
    (net (code "56") (name "Net-(LED3-A)") (class "Default")
      (node (ref "LED3") (pin "2") (pinfunction "A_2") (pintype "passive"))
      (node (ref "R3") (pin "1") (pinfunction "1_1") (pintype "passive"))
    )
    (net (code "57") (name "Net-(LED4-A)") (class "Default")
      (node (ref "LED4") (pin "2") (pinfunction "A_2") (pintype "passive"))
      (node (ref "R4") (pin "2") (pinfunction "2_2") (pintype "passive"))
    )
    (net (code "58") (name "Net-(LED5-A)") (class "Default")
      (node (ref "LED5") (pin "2") (pinfunction "A_2") (pintype "passive"))
      (node (ref "R5") (pin "1") (pinfunction "1_1") (pintype "passive"))
    )
    (net (code "59") (name "Net-(LED6-A)") (class "Default")
      (node (ref "LED6") (pin "2") (pinfunction "A_2") (pintype "passive"))
      (node (ref "R6") (pin "1") (pinfunction "1_1") (pintype "passive"))
    )
    (net (code "60") (name "POWER_VIN") (class "Default")
      (node (ref "H3") (pin "17") (pinfunction "17_17") (pintype "passive"))
      (node (ref "R5") (pin "2") (pinfunction "2_2") (pintype "passive"))
      (node (ref "R7") (pin "1") (pinfunction "1_1") (pintype "passive"))
      (node (ref "U1") (pin "13") (pinfunction "13_13") (pintype "passive"))
      (node (ref "U2") (pin "18") (pinfunction "18_18") (pintype "passive"))
    )
    (net (code "61") (name "V_BAT") (class "Default")
      (node (ref "H3") (pin "4") (pinfunction "4_4") (pintype "passive"))
      (node (ref "R16") (pin "1") (pinfunction "1_1") (pintype "passive"))
      (node (ref "R4") (pin "1") (pinfunction "1_1") (pintype "passive"))
      (node (ref "U1") (pin "39") (pinfunction "39_39") (pintype "passive"))
      (node (ref "U1") (pin "40") (pinfunction "40_40") (pintype "passive"))
      (node (ref "U2") (pin "51") (pinfunction "51_51") (pintype "passive"))
      (node (ref "U2") (pin "52") (pinfunction "52_52") (pintype "passive"))
    )
    (net (code "62") (name "V_CAP") (class "Default")
      (node (ref "H3") (pin "22") (pinfunction "22_22") (pintype "passive"))
      (node (ref "R9") (pin "1") (pinfunction "1_1") (pintype "passive"))
      (node (ref "U1") (pin "18") (pinfunction "18_18") (pintype "passive"))
      (node (ref "U2") (pin "13") (pinfunction "13_13") (pintype "passive"))
    )
    (net (code "63") (name "unconnected-(H4-Pad21)") (class "Default")
      (node (ref "H4") (pin "21") (pinfunction "21_21") (pintype "passive+no_connect"))
    )
    (net (code "64") (name "unconnected-(H4-Pad23)") (class "Default")
      (node (ref "H4") (pin "23") (pinfunction "23_23") (pintype "passive+no_connect"))
    )
    (net (code "65") (name "unconnected-(H4-Pad24)") (class "Default")
      (node (ref "H4") (pin "24") (pinfunction "24_24") (pintype "passive+no_connect"))
    )
    (net (code "66") (name "unconnected-(H4-Pad25)") (class "Default")
      (node (ref "H4") (pin "25") (pinfunction "25_25") (pintype "passive+no_connect"))
    )
  )
)
